# MT6816_Angle_Encoder.net
KiCad netlist of a schematic drawn in Altium Designer
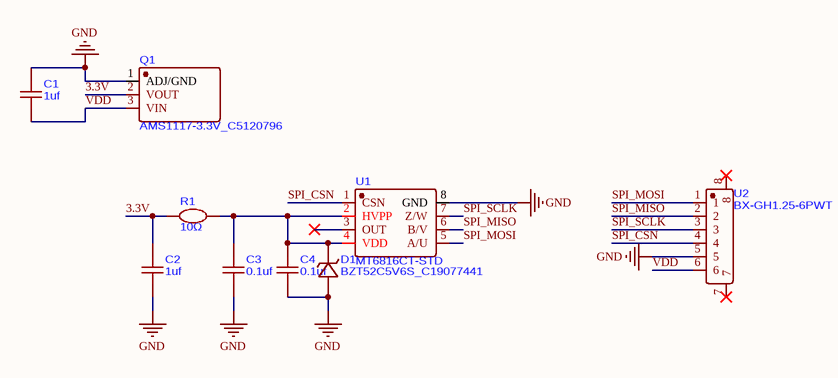
[diagram p0: MT6816_Angle_Encoder.SchDoc]

(export (version "E")
  (design (tool "Eeschema 10.0.6"))
  (components
    (comp (ref "C1")
      (value "1uf")
      (footprint "C0402")
      (libsource (lib "MT6816_Angle_Encoder") (part "CC0402KRX6S5BB225"))
    )
    (comp (ref "C2")
      (value "1uf")
      (footprint "C0402")
      (libsource (lib "MT6816_Angle_Encoder") (part "CC0402KRX6S5BB225"))
    )
    (comp (ref "C3")
      (value "0.1uf")
      (footprint "C0402")
      (libsource (lib "MT6816_Angle_Encoder") (part "CC0402KRX6S5BB225"))
    )
    (comp (ref "C4")
      (value "0.1uf")
      (footprint "C0402")
      (libsource (lib "MT6816_Angle_Encoder") (part "CC0402KRX6S5BB225"))
    )
    (comp (ref "D1")
      (value "BZT52C5V6S_C19077441")
      (footprint "SOD-323_L1.7-W1.3-LS2.6-RD")
      (libsource (lib "MT6816_Angle_Encoder") (part "BZT52C5V6S_C19077441"))
    )
    (comp (ref "Q1")
      (value "AMS1117-3.3V_C5120796")
      (footprint "SOT-89-3_L4.5-W2.5-P1.50-LS4.2-BR")
      (libsource (lib "FOC_DRV8323") (part "AMS1117-3.3V_C5120796"))
    )
    (comp (ref "R1")
      (value "10Ω")
      (footprint "R0402")
      (libsource (lib "MT6816_Angle_Encoder") (part "PTFR0402B30K0P9"))
    )
    (comp (ref "U1")
      (value "MT6816CT-STD")
      (footprint "SOP-8_L4.9-W3.9-P1.27-LS6.0-BL")
      (libsource (lib "MT6816_Angle_Encoder") (part "MT6816CT-STD"))
    )
    (comp (ref "U2")
      (value "BX-GH1.25-6PWT")
      (footprint "CONN-SMD_6P-P1.25_BX-GH1.25-6PWT")
      (libsource (lib "MT6816_Angle_Encoder") (part "BX-GH1.25-6PWT"))
    )
  )
  (nets
    (net (code "1") (name "/3.3V") (class "Default")
      (node (ref "C2") (pin "2") (pinfunction "2_2") (pintype "passive"))
      (node (ref "Q1") (pin "2") (pinfunction "VOUT_2") (pintype "passive"))
      (node (ref "R1") (pin "2") (pinfunction "2_2") (pintype "passive"))
    )
    (net (code "2") (name "/SPI_CSN") (class "Default")
      (node (ref "U1") (pin "1") (pinfunction "CSN_1") (pintype "passive"))
      (node (ref "U2") (pin "4") (pinfunction "4_4") (pintype "passive"))
    )
    (net (code "3") (name "/SPI_MISO") (class "Default")
      (node (ref "U1") (pin "6") (pinfunction "B/V_6") (pintype "passive"))
      (node (ref "U2") (pin "2") (pinfunction "2_2") (pintype "passive"))
    )
    (net (code "4") (name "/SPI_MOSI") (class "Default")
      (node (ref "U1") (pin "5") (pinfunction "A/U_5") (pintype "passive"))
      (node (ref "U2") (pin "1") (pinfunction "1_1") (pintype "passive"))
    )
    (net (code "5") (name "/SPI_SCLK") (class "Default")
      (node (ref "U1") (pin "7") (pinfunction "Z/W_7") (pintype "passive"))
      (node (ref "U2") (pin "3") (pinfunction "3_3") (pintype "passive"))
    )
    (net (code "6") (name "/VDD") (class "Default")
      (node (ref "C1") (pin "1") (pinfunction "1_1") (pintype "passive"))
      (node (ref "Q1") (pin "3") (pinfunction "VIN_3") (pintype "passive"))
      (node (ref "U2") (pin "6") (pinfunction "6_6") (pintype "passive"))
    )
    (net (code "7") (name "GND") (class "Default")
      (node (ref "C1") (pin "2") (pinfunction "2_2") (pintype "passive"))
      (node (ref "C2") (pin "1") (pinfunction "1_1") (pintype "passive"))
      (node (ref "C3") (pin "1") (pinfunction "1_1") (pintype "passive"))
      (node (ref "C4") (pin "1") (pinfunction "1_1") (pintype "passive"))
      (node (ref "D1") (pin "2") (pinfunction "A_2") (pintype "passive"))
      (node (ref "Q1") (pin "1") (pinfunction "ADJ/GND_1") (pintype "passive"))
      (node (ref "U1") (pin "8") (pinfunction "GND_8") (pintype "passive"))
      (node (ref "U2") (pin "5") (pinfunction "5_5") (pintype "passive"))
    )
    (net (code "8") (name "Net-(D1-K)") (class "Default")
      (node (ref "C3") (pin "2") (pinfunction "2_2") (pintype "passive"))
      (node (ref "C4") (pin "2") (pinfunction "2_2") (pintype "passive"))
      (node (ref "D1") (pin "1") (pinfunction "K_1") (pintype "passive"))
      (node (ref "R1") (pin "1") (pinfunction "1_1") (pintype "passive"))
      (node (ref "U1") (pin "2") (pinfunction "HVPP_2") (pintype "passive"))
      (node (ref "U1") (pin "4") (pinfunction "VDD_4") (pintype "passive"))
    )
    (net (code "9") (name "unconnected-(U1-OUT-Pad3)") (class "Default")
      (node (ref "U1") (pin "3") (pinfunction "OUT_3") (pintype "passive+no_connect"))
    )
    (net (code "10") (name "unconnected-(U2-Pad7)") (class "Default")
      (node (ref "U2") (pin "7") (pinfunction "7_7") (pintype "passive+no_connect"))
    )
    (net (code "11") (name "unconnected-(U2-Pad8)") (class "Default")
      (node (ref "U2") (pin "8") (pinfunction "8_8") (pintype "passive+no_connect"))
    )
  )
)
